# 549-capstone.net
KiCad netlist of a schematic drawn in EAGLE
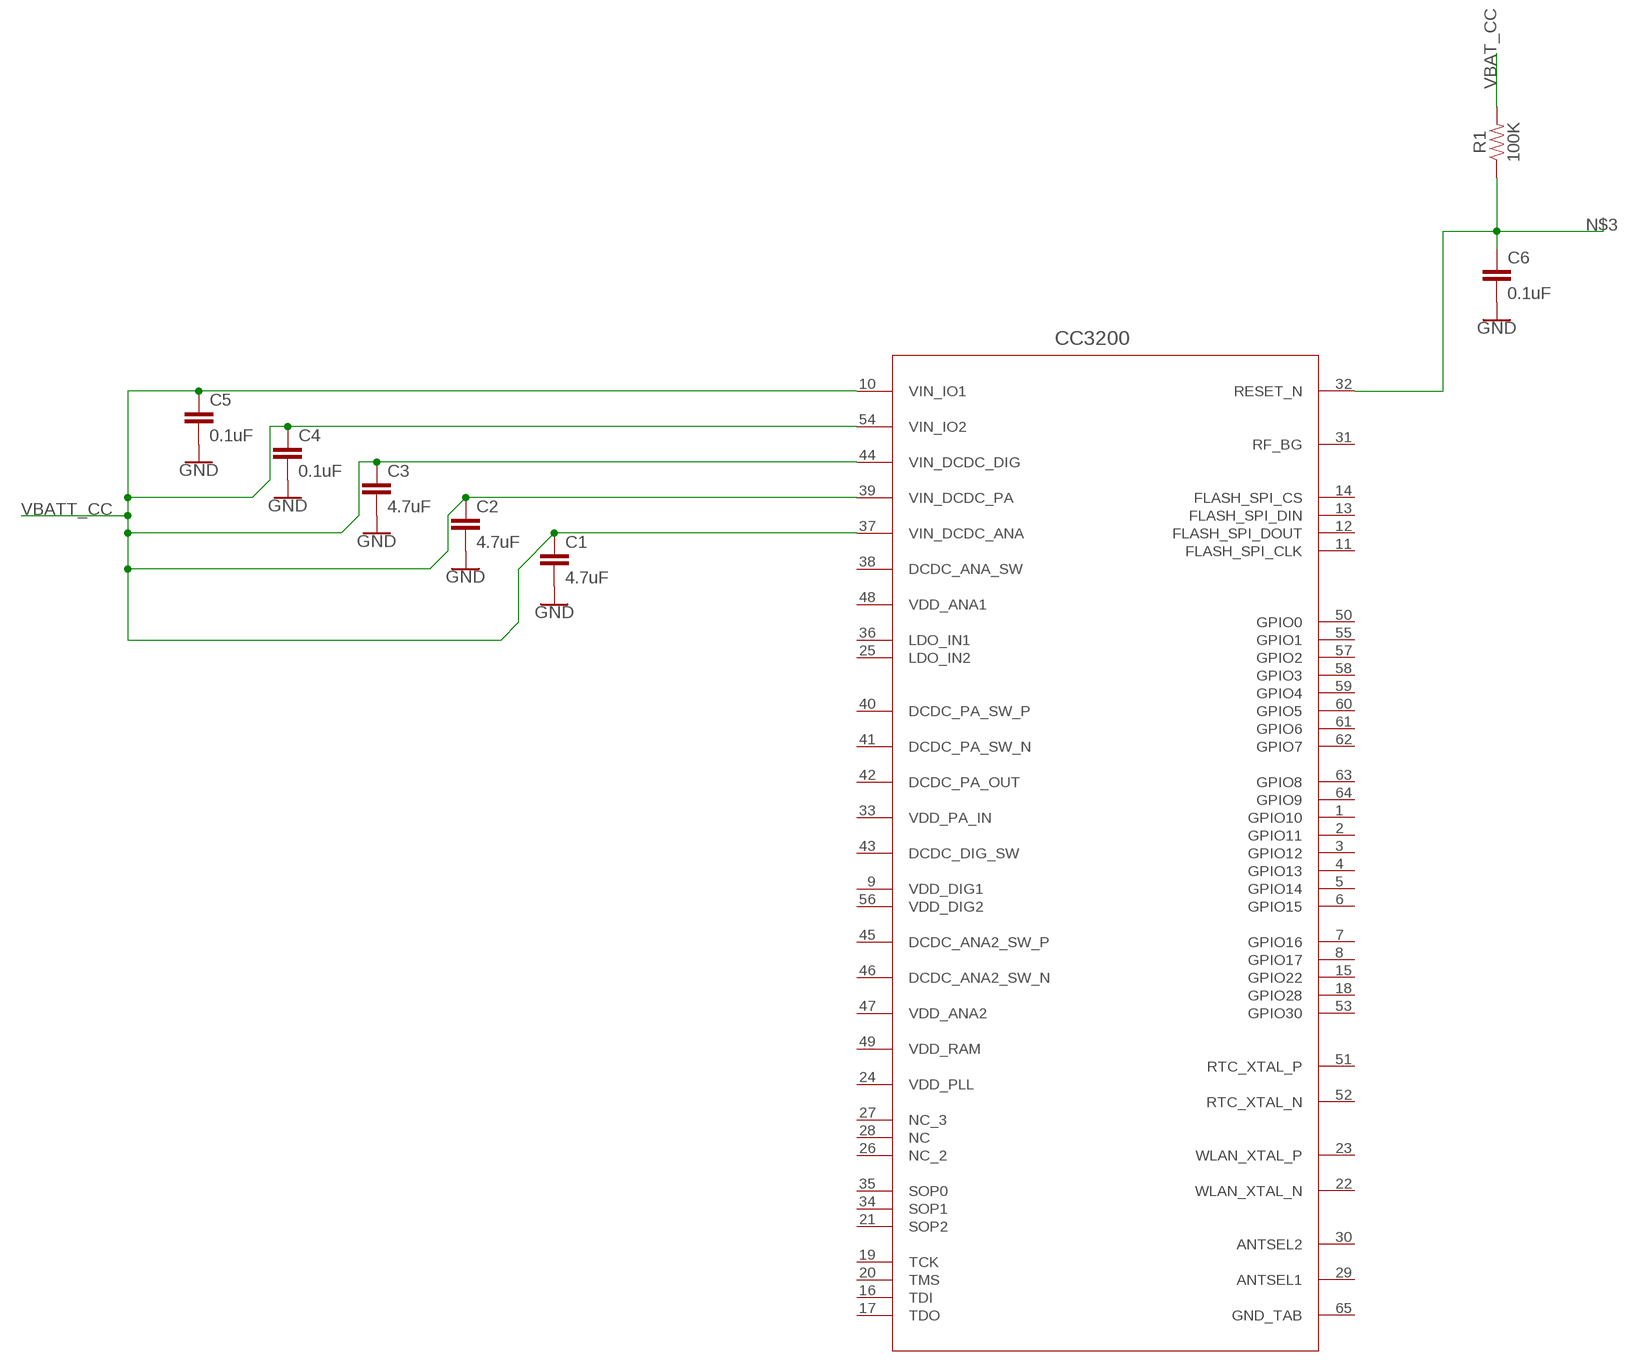
[diagram p0: schematic, sheet 1]
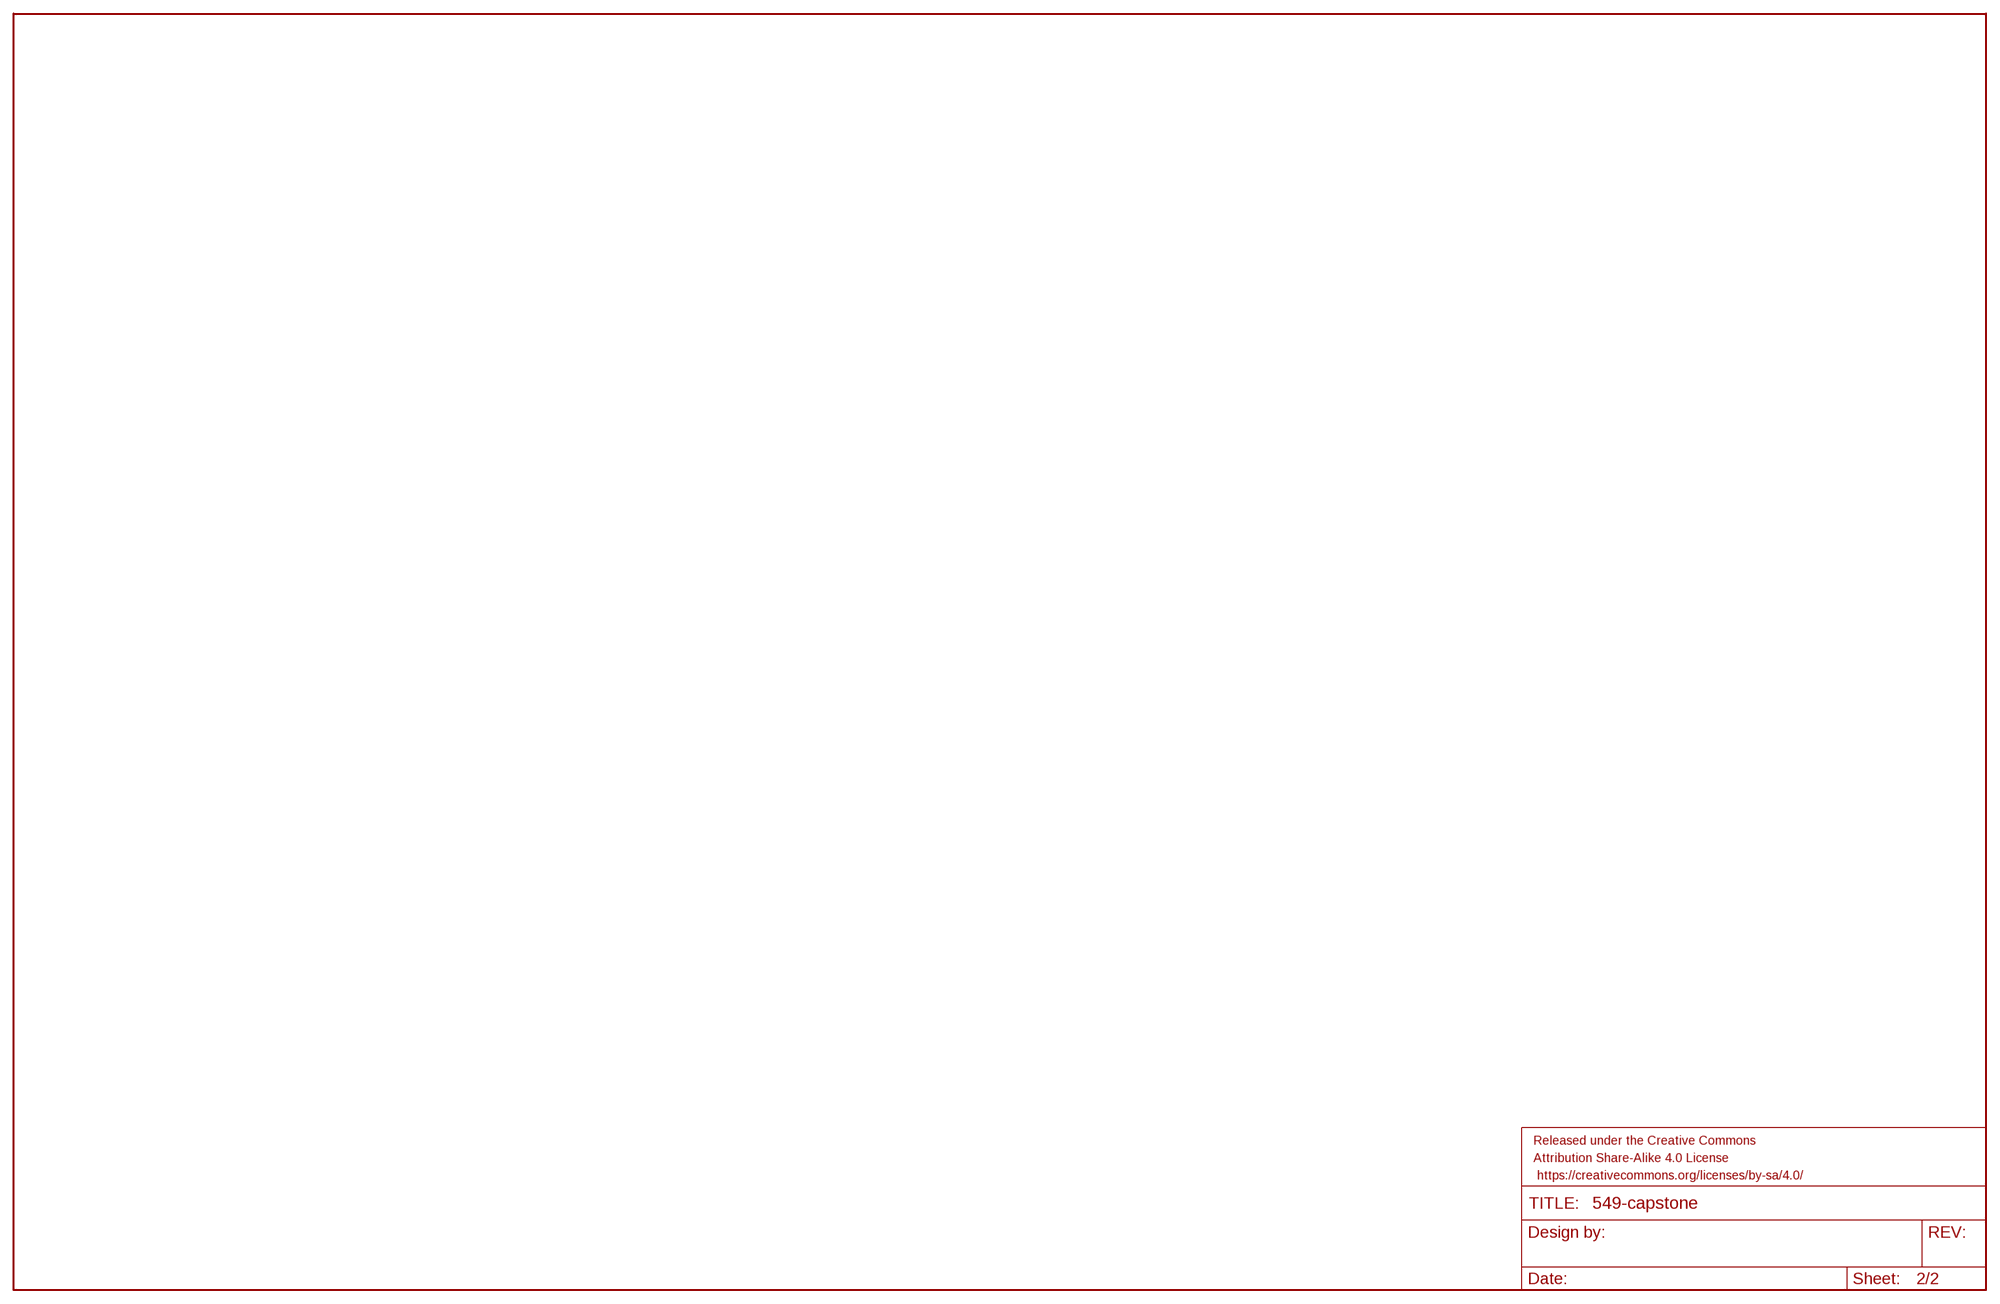
[diagram p1: schematic, sheet 2]

(export (version "E")
  (design (tool "Eeschema 10.0.6"))
  (components
    (comp (ref "FRAME2")
      (value "FRAME-LEDGER")
      (footprint "eagle-import:CREATIVE_COMMONS")
      (libsource (lib "eagle-import") (part "FRAME-LEDGER"))
    )
    (comp (ref "C1")
      (value "4.7uF")
      (footprint "eagle-import:0603")
      (libsource (lib "eagle-import") (part "4.7UF0603"))
    )
    (comp (ref "C2")
      (value "4.7uF")
      (footprint "eagle-import:0603")
      (libsource (lib "eagle-import") (part "4.7UF0603"))
    )
    (comp (ref "C3")
      (value "4.7uF")
      (footprint "eagle-import:0603")
      (libsource (lib "eagle-import") (part "4.7UF0603"))
    )
    (comp (ref "C4")
      (value "0.1uF")
      (footprint "eagle-import:0402")
      (libsource (lib "eagle-import") (part "0.1UF-0402-16V-10%"))
    )
    (comp (ref "C5")
      (value "0.1uF")
      (footprint "eagle-import:0402")
      (libsource (lib "eagle-import") (part "0.1UF-0402-16V-10%"))
    )
    (comp (ref "C6")
      (value "0.1uF")
      (footprint "eagle-import:0402")
      (libsource (lib "eagle-import") (part "0.1UF-0402-16V-10%"))
    )
    (comp (ref "CC3200")
      (value "CC3200R1M2RGCR")
      (footprint "eagle-import:RGC0064A")
      (fields
        (field (name "ALTERNATEPARTNUMBER") "CC3200R1M2RGC")
        (field (name "MANUFACTURER") "Texas Instruments")
      )
      (libsource (lib "eagle-import") (part "CC3200R1M2RGCR"))
    )
    (comp (ref "R1")
      (value "100K")
      (footprint "eagle-import:0402")
      (libsource (lib "eagle-import") (part "100KOHM-0402-1/16W-1%"))
    )
  )
  (nets
    (net (code "1") (name "DCDC_ANA_SW") (class "Default")
      (node (ref "CC3200") (pin "38") (pinfunction "DCDC_ANA_SW_38") (pintype "power_in"))
    )
    (net (code "2") (name "DCDC_DIG_SW") (class "Default")
      (node (ref "CC3200") (pin "43") (pinfunction "DCDC_DIG_SW_43") (pintype "power_in"))
    )
    (net (code "3") (name "DCDC_PA_OUT") (class "Default")
      (node (ref "CC3200") (pin "42") (pinfunction "DCDC_PA_OUT_42") (pintype "power_in"))
    )
    (net (code "4") (name "DCDC_PA_SW_N") (class "Default")
      (node (ref "CC3200") (pin "41") (pinfunction "DCDC_PA_SW_N_41") (pintype "power_in"))
    )
    (net (code "5") (name "DCDC_PA_SW_P") (class "Default")
      (node (ref "CC3200") (pin "40") (pinfunction "DCDC_PA_SW_P_40") (pintype "power_in"))
    )
    (net (code "6") (name "GND") (class "Default")
      (node (ref "C1") (pin "2") (pinfunction "2_2") (pintype "passive"))
      (node (ref "C2") (pin "2") (pinfunction "2_2") (pintype "passive"))
      (node (ref "C3") (pin "2") (pinfunction "2_2") (pintype "passive"))
      (node (ref "C4") (pin "2") (pinfunction "2_2") (pintype "passive"))
      (node (ref "C5") (pin "2") (pinfunction "2_2") (pintype "passive"))
      (node (ref "C6") (pin "2") (pinfunction "2_2") (pintype "passive"))
    )
    (net (code "7") (name "GND_TAB") (class "Default")
      (node (ref "CC3200") (pin "65") (pinfunction "GND_TAB_65") (pintype "power_in"))
    )
    (net (code "8") (name "LDO_IN1") (class "Default")
      (node (ref "CC3200") (pin "36") (pinfunction "LDO_IN1_36") (pintype "power_in"))
    )
    (net (code "9") (name "LDO_IN2") (class "Default")
      (node (ref "CC3200") (pin "25") (pinfunction "LDO_IN2_25") (pintype "power_in"))
    )
    (net (code "10") (name "N$3") (class "Default")
      (node (ref "C6") (pin "1") (pinfunction "1_1") (pintype "passive"))
      (node (ref "CC3200") (pin "32") (pinfunction "RESET_N_32") (pintype "input"))
      (node (ref "R1") (pin "1") (pinfunction "1_1") (pintype "passive"))
    )
    (net (code "11") (name "VBATT_CC") (class "Default")
      (node (ref "C1") (pin "1") (pinfunction "1_1") (pintype "passive"))
      (node (ref "C2") (pin "1") (pinfunction "1_1") (pintype "passive"))
      (node (ref "C3") (pin "1") (pinfunction "1_1") (pintype "passive"))
      (node (ref "C4") (pin "1") (pinfunction "1_1") (pintype "passive"))
      (node (ref "C5") (pin "1") (pinfunction "1_1") (pintype "passive"))
      (node (ref "CC3200") (pin "10") (pinfunction "VIN_IO1_10") (pintype "power_in"))
      (node (ref "CC3200") (pin "37") (pinfunction "VIN_DCDC_ANA_37") (pintype "power_in"))
      (node (ref "CC3200") (pin "39") (pinfunction "VIN_DCDC_PA_39") (pintype "power_in"))
      (node (ref "CC3200") (pin "44") (pinfunction "VIN_DCDC_DIG_44") (pintype "power_in"))
      (node (ref "CC3200") (pin "54") (pinfunction "VIN_IO2_54") (pintype "power_in"))
    )
    (net (code "12") (name "VBAT_CC") (class "Default")
      (node (ref "R1") (pin "2") (pinfunction "2_2") (pintype "passive"))
    )
    (net (code "13") (name "VDD_ANA1") (class "Default")
      (node (ref "CC3200") (pin "48") (pinfunction "VDD_ANA1_48") (pintype "power_in"))
    )
    (net (code "14") (name "VDD_ANA2") (class "Default")
      (node (ref "CC3200") (pin "47") (pinfunction "VDD_ANA2_47") (pintype "power_in"))
    )
    (net (code "15") (name "VDD_DIG1") (class "Default")
      (node (ref "CC3200") (pin "9") (pinfunction "VDD_DIG1_9") (pintype "power_in"))
    )
    (net (code "16") (name "VDD_DIG2") (class "Default")
      (node (ref "CC3200") (pin "56") (pinfunction "VDD_DIG2_56") (pintype "power_in"))
    )
    (net (code "17") (name "VDD_PA_IN") (class "Default")
      (node (ref "CC3200") (pin "33") (pinfunction "VDD_PA_IN_33") (pintype "power_in"))
    )
    (net (code "18") (name "VDD_PLL") (class "Default")
      (node (ref "CC3200") (pin "24") (pinfunction "VDD_PLL_24") (pintype "power_in"))
    )
    (net (code "19") (name "VDD_RAM") (class "Default")
      (node (ref "CC3200") (pin "49") (pinfunction "VDD_RAM_49") (pintype "power_in"))
    )
    (net (code "20") (name "unconnected-(CC3200-ANTSEL1-Pad29)") (class "Default")
      (node (ref "CC3200") (pin "29") (pinfunction "ANTSEL1_29") (pintype "output"))
    )
    (net (code "21") (name "unconnected-(CC3200-ANTSEL2-Pad30)") (class "Default")
      (node (ref "CC3200") (pin "30") (pinfunction "ANTSEL2_30") (pintype "output"))
    )
    (net (code "22") (name "unconnected-(CC3200-DCDC_ANA2_SW_N-Pad46)") (class "Default")
      (node (ref "CC3200") (pin "46") (pinfunction "DCDC_ANA2_SW_N_46") (pintype "bidirectional"))
    )
    (net (code "23") (name "unconnected-(CC3200-DCDC_ANA2_SW_P-Pad45)") (class "Default")
      (node (ref "CC3200") (pin "45") (pinfunction "DCDC_ANA2_SW_P_45") (pintype "bidirectional"))
    )
    (net (code "24") (name "unconnected-(CC3200-FLASH_SPI_CLK-Pad11)") (class "Default")
      (node (ref "CC3200") (pin "11") (pinfunction "FLASH_SPI_CLK_11") (pintype "output"))
    )
    (net (code "25") (name "unconnected-(CC3200-FLASH_SPI_CS-Pad14)") (class "Default")
      (node (ref "CC3200") (pin "14") (pinfunction "FLASH_SPI_CS_14") (pintype "output"))
    )
    (net (code "26") (name "unconnected-(CC3200-FLASH_SPI_DIN-Pad13)") (class "Default")
      (node (ref "CC3200") (pin "13") (pinfunction "FLASH_SPI_DIN_13") (pintype "input"))
    )
    (net (code "27") (name "unconnected-(CC3200-FLASH_SPI_DOUT-Pad12)") (class "Default")
      (node (ref "CC3200") (pin "12") (pinfunction "FLASH_SPI_DOUT_12") (pintype "output"))
    )
    (net (code "28") (name "unconnected-(CC3200-GPIO0-Pad50)") (class "Default")
      (node (ref "CC3200") (pin "50") (pinfunction "GPIO0_50") (pintype "bidirectional"))
    )
    (net (code "29") (name "unconnected-(CC3200-GPIO1-Pad55)") (class "Default")
      (node (ref "CC3200") (pin "55") (pinfunction "GPIO1_55") (pintype "bidirectional"))
    )
    (net (code "30") (name "unconnected-(CC3200-GPIO2-Pad57)") (class "Default")
      (node (ref "CC3200") (pin "57") (pinfunction "GPIO2_57") (pintype "bidirectional"))
    )
    (net (code "31") (name "unconnected-(CC3200-GPIO3-Pad58)") (class "Default")
      (node (ref "CC3200") (pin "58") (pinfunction "GPIO3_58") (pintype "bidirectional"))
    )
    (net (code "32") (name "unconnected-(CC3200-GPIO4-Pad59)") (class "Default")
      (node (ref "CC3200") (pin "59") (pinfunction "GPIO4_59") (pintype "bidirectional"))
    )
    (net (code "33") (name "unconnected-(CC3200-GPIO5-Pad60)") (class "Default")
      (node (ref "CC3200") (pin "60") (pinfunction "GPIO5_60") (pintype "bidirectional"))
    )
    (net (code "34") (name "unconnected-(CC3200-GPIO6-Pad61)") (class "Default")
      (node (ref "CC3200") (pin "61") (pinfunction "GPIO6_61") (pintype "bidirectional"))
    )
    (net (code "35") (name "unconnected-(CC3200-GPIO7-Pad62)") (class "Default")
      (node (ref "CC3200") (pin "62") (pinfunction "GPIO7_62") (pintype "bidirectional"))
    )
    (net (code "36") (name "unconnected-(CC3200-GPIO8-Pad63)") (class "Default")
      (node (ref "CC3200") (pin "63") (pinfunction "GPIO8_63") (pintype "bidirectional"))
    )
    (net (code "37") (name "unconnected-(CC3200-GPIO9-Pad64)") (class "Default")
      (node (ref "CC3200") (pin "64") (pinfunction "GPIO9_64") (pintype "bidirectional"))
    )
    (net (code "38") (name "unconnected-(CC3200-GPIO10-Pad1)") (class "Default")
      (node (ref "CC3200") (pin "1") (pinfunction "GPIO10_1") (pintype "bidirectional"))
    )
    (net (code "39") (name "unconnected-(CC3200-GPIO11-Pad2)") (class "Default")
      (node (ref "CC3200") (pin "2") (pinfunction "GPIO11_2") (pintype "bidirectional"))
    )
    (net (code "40") (name "unconnected-(CC3200-GPIO12-Pad3)") (class "Default")
      (node (ref "CC3200") (pin "3") (pinfunction "GPIO12_3") (pintype "bidirectional"))
    )
    (net (code "41") (name "unconnected-(CC3200-GPIO13-Pad4)") (class "Default")
      (node (ref "CC3200") (pin "4") (pinfunction "GPIO13_4") (pintype "bidirectional"))
    )
    (net (code "42") (name "unconnected-(CC3200-GPIO14-Pad5)") (class "Default")
      (node (ref "CC3200") (pin "5") (pinfunction "GPIO14_5") (pintype "bidirectional"))
    )
    (net (code "43") (name "unconnected-(CC3200-GPIO15-Pad6)") (class "Default")
      (node (ref "CC3200") (pin "6") (pinfunction "GPIO15_6") (pintype "bidirectional"))
    )
    (net (code "44") (name "unconnected-(CC3200-GPIO16-Pad7)") (class "Default")
      (node (ref "CC3200") (pin "7") (pinfunction "GPIO16_7") (pintype "bidirectional"))
    )
    (net (code "45") (name "unconnected-(CC3200-GPIO17-Pad8)") (class "Default")
      (node (ref "CC3200") (pin "8") (pinfunction "GPIO17_8") (pintype "bidirectional"))
    )
    (net (code "46") (name "unconnected-(CC3200-GPIO22-Pad15)") (class "Default")
      (node (ref "CC3200") (pin "15") (pinfunction "GPIO22_15") (pintype "bidirectional"))
    )
    (net (code "47") (name "unconnected-(CC3200-GPIO28-Pad18)") (class "Default")
      (node (ref "CC3200") (pin "18") (pinfunction "GPIO28_18") (pintype "bidirectional"))
    )
    (net (code "48") (name "unconnected-(CC3200-GPIO30-Pad53)") (class "Default")
      (node (ref "CC3200") (pin "53") (pinfunction "GPIO30_53") (pintype "bidirectional"))
    )
    (net (code "49") (name "unconnected-(CC3200-NC-Pad28)") (class "Default")
      (node (ref "CC3200") (pin "28") (pinfunction "NC_28") (pintype "passive"))
    )
    (net (code "50") (name "unconnected-(CC3200-NC_2-Pad26)") (class "Default")
      (node (ref "CC3200") (pin "26") (pinfunction "NC_2_26") (pintype "passive"))
    )
    (net (code "51") (name "unconnected-(CC3200-NC_3-Pad27)") (class "Default")
      (node (ref "CC3200") (pin "27") (pinfunction "NC_3_27") (pintype "passive"))
    )
    (net (code "52") (name "unconnected-(CC3200-RF_BG-Pad31)") (class "Default")
      (node (ref "CC3200") (pin "31") (pinfunction "RF_BG_31") (pintype "passive"))
    )
    (net (code "53") (name "unconnected-(CC3200-RTC_XTAL_N-Pad52)") (class "Default")
      (node (ref "CC3200") (pin "52") (pinfunction "RTC_XTAL_N_52") (pintype "passive"))
    )
    (net (code "54") (name "unconnected-(CC3200-RTC_XTAL_P-Pad51)") (class "Default")
      (node (ref "CC3200") (pin "51") (pinfunction "RTC_XTAL_P_51") (pintype "passive"))
    )
    (net (code "55") (name "unconnected-(CC3200-SOP0-Pad35)") (class "Default")
      (node (ref "CC3200") (pin "35") (pinfunction "SOP0_35") (pintype "input"))
    )
    (net (code "56") (name "unconnected-(CC3200-SOP1-Pad34)") (class "Default")
      (node (ref "CC3200") (pin "34") (pinfunction "SOP1_34") (pintype "input"))
    )
    (net (code "57") (name "unconnected-(CC3200-SOP2-Pad21)") (class "Default")
      (node (ref "CC3200") (pin "21") (pinfunction "SOP2_21") (pintype "output"))
    )
    (net (code "58") (name "unconnected-(CC3200-TCK-Pad19)") (class "Default")
      (node (ref "CC3200") (pin "19") (pinfunction "TCK_19") (pintype "bidirectional"))
    )
    (net (code "59") (name "unconnected-(CC3200-TDI-Pad16)") (class "Default")
      (node (ref "CC3200") (pin "16") (pinfunction "TDI_16") (pintype "bidirectional"))
    )
    (net (code "60") (name "unconnected-(CC3200-TDO-Pad17)") (class "Default")
      (node (ref "CC3200") (pin "17") (pinfunction "TDO_17") (pintype "bidirectional"))
    )
    (net (code "61") (name "unconnected-(CC3200-TMS-Pad20)") (class "Default")
      (node (ref "CC3200") (pin "20") (pinfunction "TMS_20") (pintype "bidirectional"))
    )
    (net (code "62") (name "unconnected-(CC3200-WLAN_XTAL_N-Pad22)") (class "Default")
      (node (ref "CC3200") (pin "22") (pinfunction "WLAN_XTAL_N_22") (pintype "passive"))
    )
    (net (code "63") (name "unconnected-(CC3200-WLAN_XTAL_P-Pad23)") (class "Default")
      (node (ref "CC3200") (pin "23") (pinfunction "WLAN_XTAL_P_23") (pintype "passive"))
    )
  )
)
